# DACs.net
KiCad netlist of a schematic drawn in Altium Designer
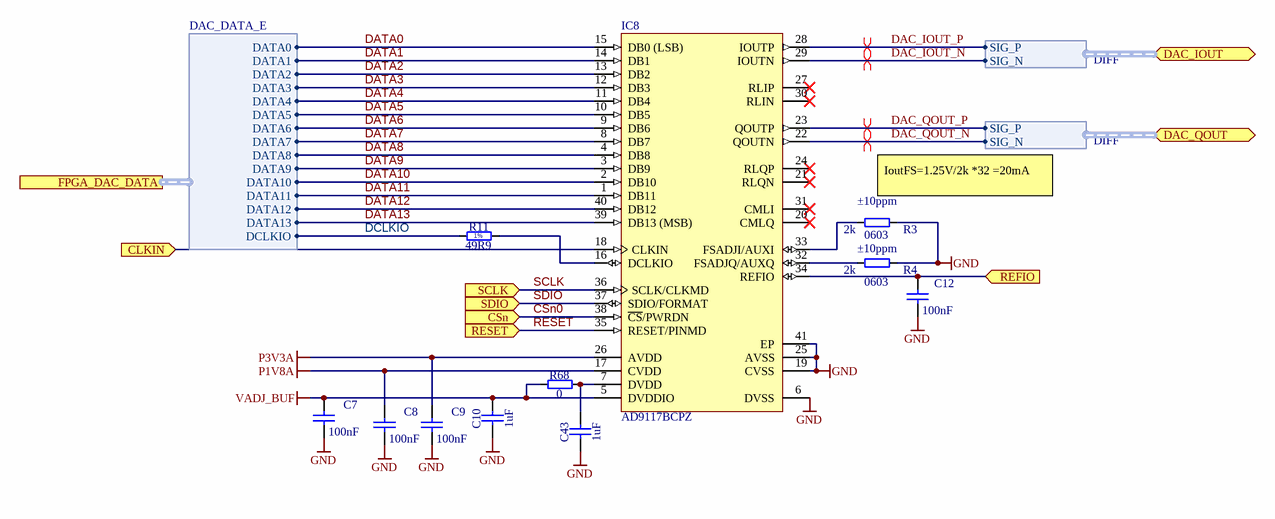
[diagram p0: DACs.SchDoc]

(export (version "E")
  (design (tool "Eeschema 10.0.6"))
  (components
    (comp (ref "C7")
      (value "100nF")
      (footprint "CAPC1005X55N")
      (description "Non-polarised capacitor")
      (fields
        (field (name "PART NUMBER") "CC0402_100NF_16V_10%_X7R")
        (field (name "VOLTAGE") "16V")
        (field (name "AUTHOR") "CERN DEM JLC")
      )
      (libsource (lib "Capacitors") (part "Capacitor - non polarized"))
    )
    (comp (ref "C8")
      (value "100nF")
      (footprint "CAPC1005X55N")
      (description "Non-polarised capacitor")
      (fields
        (field (name "PART NUMBER") "CC0402_100NF_16V_10%_X7R")
        (field (name "VOLTAGE") "16V")
        (field (name "AUTHOR") "CERN DEM JLC")
      )
      (libsource (lib "Capacitors") (part "Capacitor - non polarized"))
    )
    (comp (ref "C9")
      (value "100nF")
      (footprint "CAPC1005X55N")
      (description "Non-polarised capacitor")
      (fields
        (field (name "PART NUMBER") "CC0402_100NF_16V_10%_X7R")
        (field (name "VOLTAGE") "16V")
        (field (name "AUTHOR") "CERN DEM JLC")
      )
      (libsource (lib "Capacitors") (part "Capacitor - non polarized"))
    )
    (comp (ref "C10")
      (value "1uF")
      (footprint "CAPC1608X87N")
      (description "Non-polarised capacitor")
      (fields
        (field (name "PART NUMBER") "CC0603_1UF_25V_10%_X7R")
        (field (name "VOLTAGE") "25V")
        (field (name "AUTHOR") "CERN DEM JLC")
      )
      (libsource (lib "Capacitors") (part "Capacitor - non polarized"))
    )
    (comp (ref "C12")
      (value "100nF")
      (footprint "CAPC1005X55N")
      (description "Non-polarised capacitor")
      (fields
        (field (name "PART NUMBER") "CC0402_100NF_16V_10%_X7R")
        (field (name "VOLTAGE") "16V")
        (field (name "AUTHOR") "CERN DEM JLC")
      )
      (libsource (lib "Capacitors") (part "Capacitor - non polarized"))
    )
    (comp (ref "C43")
      (value "1uF")
      (footprint "CAPC1608X87N")
      (description "Non-polarised capacitor")
      (fields
        (field (name "PART NUMBER") "CC0603_1UF_25V_10%_X7R")
        (field (name "VOLTAGE") "25V")
        (field (name "AUTHOR") "CERN DEM JLC")
      )
      (libsource (lib "Capacitors") (part "Capacitor - non polarized"))
    )
    (comp (ref "IC8")
      (value "AD9117BCPZ")
      (footprint "CP-40-1_N")
      (description "Dual 14-Bit Low Power TxDAC Digital-to-Analog Converter, 0 to +70 degC, CP-40-1, Pb-Free, Tray")
      (fields (field (name "MANUFACTURER") "Analog Devices") (field (name "GENERIC PART NUMBER") "AD9117"))
      (libsource (lib "Altium Content Vault") (part "ADI-AD9117-CP-40-1"))
    )
    (comp (ref "R3")
      (value "2k")
      (footprint "RESC1608X55N")
      (description "Resistor - 0.1%")
      (fields
        (field (name "PART NUMBER") "R0603_2K_0.1%_0.063W_10PPM")
        (field (name "POWER") "0.063W")
        (field (name "TC") "±10ppm")
        (field (name "CASE") "0603")
        (field (name "AUTHOR") "CERN DEM JLC")
      )
      (libsource (lib "Resistors") (part "Resistor - 0.1%"))
    )
    (comp (ref "R4")
      (value "2k")
      (footprint "RESC1608X55N")
      (description "Resistor - 0.1%")
      (fields
        (field (name "PART NUMBER") "R0603_2K_0.1%_0.063W_10PPM")
        (field (name "POWER") "0.063W")
        (field (name "TC") "±10ppm")
        (field (name "CASE") "0603")
        (field (name "AUTHOR") "CERN DEM JLC")
      )
      (libsource (lib "Resistors") (part "Resistor - 0.1%"))
    )
    (comp (ref "R11")
      (value "49R9")
      (footprint "RESC0603X28N")
      (description "Resistor - 1%")
      (fields
        (field (name "PART NUMBER") "R0201_49R9_1%_0.05W_200PPM")
        (field (name "POWER") "0.05W")
        (field (name "AUTHOR") "CERN DEM BC")
      )
      (libsource (lib "Resistors") (part "Resistor - 1%"))
    )
    (comp (ref "R68")
      (value "0")
      (footprint "RESC1005X40N")
      (description "Resistor")
      (fields
        (field (name "PART NUMBER") "R0402_0R_JUMPER")
        (field (name "MANUFACTURER") "GENERIC")
        (field (name "AUTHOR") "CERN DEM JLC")
      )
      (libsource (lib "Resistors") (part "Resistor"))
    )
  )
  (nets
    (net (code "3") (name "/CLKIN") (class "Default")
      (node (ref "IC8") (pin "18") (pinfunction "CLKIN_18") (pintype "input"))
    )
    (net (code "4") (name "/CSn0") (class "Default")
      (node (ref "IC8") (pin "38") (pinfunction "~{CS}/PWRDN_38") (pintype "input"))
    )
    (net (code "5") (name "/DAC_IOUT_N") (class "Default")
      (node (ref "IC8") (pin "29") (pinfunction "IOUTN_29") (pintype "output"))
    )
    (net (code "6") (name "/DAC_IOUT_P") (class "Default")
      (node (ref "IC8") (pin "28") (pinfunction "IOUTP_28") (pintype "output"))
    )
    (net (code "7") (name "/DAC_QOUT_N") (class "Default")
      (node (ref "IC8") (pin "22") (pinfunction "QOUTN_22") (pintype "output"))
    )
    (net (code "8") (name "/DAC_QOUT_P") (class "Default")
      (node (ref "IC8") (pin "23") (pinfunction "QOUTP_23") (pintype "output"))
    )
    (net (code "9") (name "/DATA0") (class "Default")
      (node (ref "IC8") (pin "15") (pinfunction "DB0_(LSB)_15") (pintype "input"))
    )
    (net (code "10") (name "/DATA1") (class "Default")
      (node (ref "IC8") (pin "14") (pinfunction "DB1_14") (pintype "input"))
    )
    (net (code "11") (name "/DATA2") (class "Default")
      (node (ref "IC8") (pin "13") (pinfunction "DB2_13") (pintype "input"))
    )
    (net (code "12") (name "/DATA3") (class "Default")
      (node (ref "IC8") (pin "12") (pinfunction "DB3_12") (pintype "input"))
    )
    (net (code "13") (name "/DATA4") (class "Default")
      (node (ref "IC8") (pin "11") (pinfunction "DB4_11") (pintype "input"))
    )
    (net (code "14") (name "/DATA5") (class "Default")
      (node (ref "IC8") (pin "10") (pinfunction "DB5_10") (pintype "input"))
    )
    (net (code "15") (name "/DATA6") (class "Default")
      (node (ref "IC8") (pin "9") (pinfunction "DB6_9") (pintype "input"))
    )
    (net (code "16") (name "/DATA7") (class "Default")
      (node (ref "IC8") (pin "8") (pinfunction "DB7_8") (pintype "input"))
    )
    (net (code "17") (name "/DATA8") (class "Default")
      (node (ref "IC8") (pin "4") (pinfunction "DB8_4") (pintype "input"))
    )
    (net (code "18") (name "/DATA9") (class "Default")
      (node (ref "IC8") (pin "3") (pinfunction "DB9_3") (pintype "input"))
    )
    (net (code "19") (name "/DATA10") (class "Default")
      (node (ref "IC8") (pin "2") (pinfunction "DB10_2") (pintype "input"))
    )
    (net (code "20") (name "/DATA11") (class "Default")
      (node (ref "IC8") (pin "1") (pinfunction "DB11_1") (pintype "input"))
    )
    (net (code "21") (name "/DATA12") (class "Default")
      (node (ref "IC8") (pin "40") (pinfunction "DB12_40") (pintype "input"))
    )
    (net (code "22") (name "/DATA13") (class "Default")
      (node (ref "IC8") (pin "39") (pinfunction "DB13_(MSB)_39") (pintype "input"))
    )
    (net (code "23") (name "/DCLKIO") (class "Default")
      (node (ref "R11") (pin "1") (pinfunction "1_1") (pintype "passive"))
    )
    (net (code "24") (name "/REFIO") (class "Default")
      (node (ref "C12") (pin "1") (pinfunction "1_1") (pintype "passive"))
      (node (ref "IC8") (pin "34") (pinfunction "REFIO_34") (pintype "bidirectional"))
    )
    (net (code "25") (name "/RESET") (class "Default")
      (node (ref "IC8") (pin "35") (pinfunction "RESET/PINMD_35") (pintype "input"))
    )
    (net (code "26") (name "/SCLK") (class "Default")
      (node (ref "IC8") (pin "36") (pinfunction "SCLK/CLKMD_36") (pintype "input"))
    )
    (net (code "27") (name "/SDIO") (class "Default")
      (node (ref "IC8") (pin "37") (pinfunction "SDIO/FORMAT_37") (pintype "bidirectional"))
    )
    (net (code "30") (name "GND") (class "Default")
      (node (ref "C10") (pin "1") (pinfunction "1_1") (pintype "passive"))
      (node (ref "C12") (pin "2") (pinfunction "2_2") (pintype "passive"))
      (node (ref "C43") (pin "1") (pinfunction "1_1") (pintype "passive"))
      (node (ref "C7") (pin "2") (pinfunction "2_2") (pintype "passive"))
      (node (ref "C8") (pin "2") (pinfunction "2_2") (pintype "passive"))
      (node (ref "C9") (pin "2") (pinfunction "2_2") (pintype "passive"))
      (node (ref "IC8") (pin "19") (pinfunction "CVSS_19") (pintype "power_in"))
      (node (ref "IC8") (pin "25") (pinfunction "AVSS_25") (pintype "power_in"))
      (node (ref "IC8") (pin "41") (pinfunction "EP_41") (pintype "power_in"))
      (node (ref "IC8") (pin "6") (pinfunction "DVSS_6") (pintype "power_in"))
      (node (ref "R3") (pin "2") (pinfunction "2_2") (pintype "passive"))
      (node (ref "R4") (pin "2") (pinfunction "2_2") (pintype "passive"))
    )
    (net (code "31") (name "Net-(IC8-DCLKIO)") (class "Default")
      (node (ref "IC8") (pin "16") (pinfunction "DCLKIO_16") (pintype "bidirectional"))
      (node (ref "R11") (pin "2") (pinfunction "2_2") (pintype "passive"))
    )
    (net (code "32") (name "Net-(IC8-DVDD)") (class "Default")
      (node (ref "C43") (pin "2") (pinfunction "2_2") (pintype "passive"))
      (node (ref "IC8") (pin "7") (pinfunction "DVDD_7") (pintype "power_in"))
      (node (ref "R68") (pin "2") (pinfunction "2_2") (pintype "passive"))
    )
    (net (code "33") (name "Net-(IC8-FSADJI{slash}AUXI)") (class "Default")
      (node (ref "IC8") (pin "33") (pinfunction "FSADJI/AUXI_33") (pintype "bidirectional"))
      (node (ref "R3") (pin "1") (pinfunction "1_1") (pintype "passive"))
    )
    (net (code "34") (name "Net-(IC8-FSADJQ{slash}AUXQ)") (class "Default")
      (node (ref "IC8") (pin "32") (pinfunction "FSADJQ/AUXQ_32") (pintype "bidirectional"))
      (node (ref "R4") (pin "1") (pinfunction "1_1") (pintype "passive"))
    )
    (net (code "35") (name "P1V8A") (class "Default")
      (node (ref "C8") (pin "1") (pinfunction "1_1") (pintype "passive"))
      (node (ref "IC8") (pin "17") (pinfunction "CVDD_17") (pintype "power_in"))
    )
    (net (code "36") (name "P3V3A") (class "Default")
      (node (ref "C9") (pin "1") (pinfunction "1_1") (pintype "passive"))
      (node (ref "IC8") (pin "26") (pinfunction "AVDD_26") (pintype "power_in"))
    )
    (net (code "37") (name "VADJ_BUF") (class "Default")
      (node (ref "C10") (pin "2") (pinfunction "2_2") (pintype "passive"))
      (node (ref "C7") (pin "1") (pinfunction "1_1") (pintype "passive"))
      (node (ref "IC8") (pin "5") (pinfunction "DVDDIO_5") (pintype "power_in"))
      (node (ref "R68") (pin "1") (pinfunction "1_1") (pintype "passive"))
    )
    (net (code "38") (name "unconnected-(IC8-CMLI-Pad31)") (class "Default")
      (node (ref "IC8") (pin "31") (pinfunction "CMLI_31") (pintype "passive+no_connect"))
    )
    (net (code "39") (name "unconnected-(IC8-CMLQ-Pad20)") (class "Default")
      (node (ref "IC8") (pin "20") (pinfunction "CMLQ_20") (pintype "passive+no_connect"))
    )
    (net (code "40") (name "unconnected-(IC8-RLIN-Pad30)") (class "Default")
      (node (ref "IC8") (pin "30") (pinfunction "RLIN_30") (pintype "passive+no_connect"))
    )
    (net (code "41") (name "unconnected-(IC8-RLIP-Pad27)") (class "Default")
      (node (ref "IC8") (pin "27") (pinfunction "RLIP_27") (pintype "passive+no_connect"))
    )
    (net (code "42") (name "unconnected-(IC8-RLQN-Pad21)") (class "Default")
      (node (ref "IC8") (pin "21") (pinfunction "RLQN_21") (pintype "passive+no_connect"))
    )
    (net (code "43") (name "unconnected-(IC8-RLQP-Pad24)") (class "Default")
      (node (ref "IC8") (pin "24") (pinfunction "RLQP_24") (pintype "passive+no_connect"))
    )
  )
)
